# CBB-Proto-r02.net
KiCad netlist of a schematic drawn in EAGLE
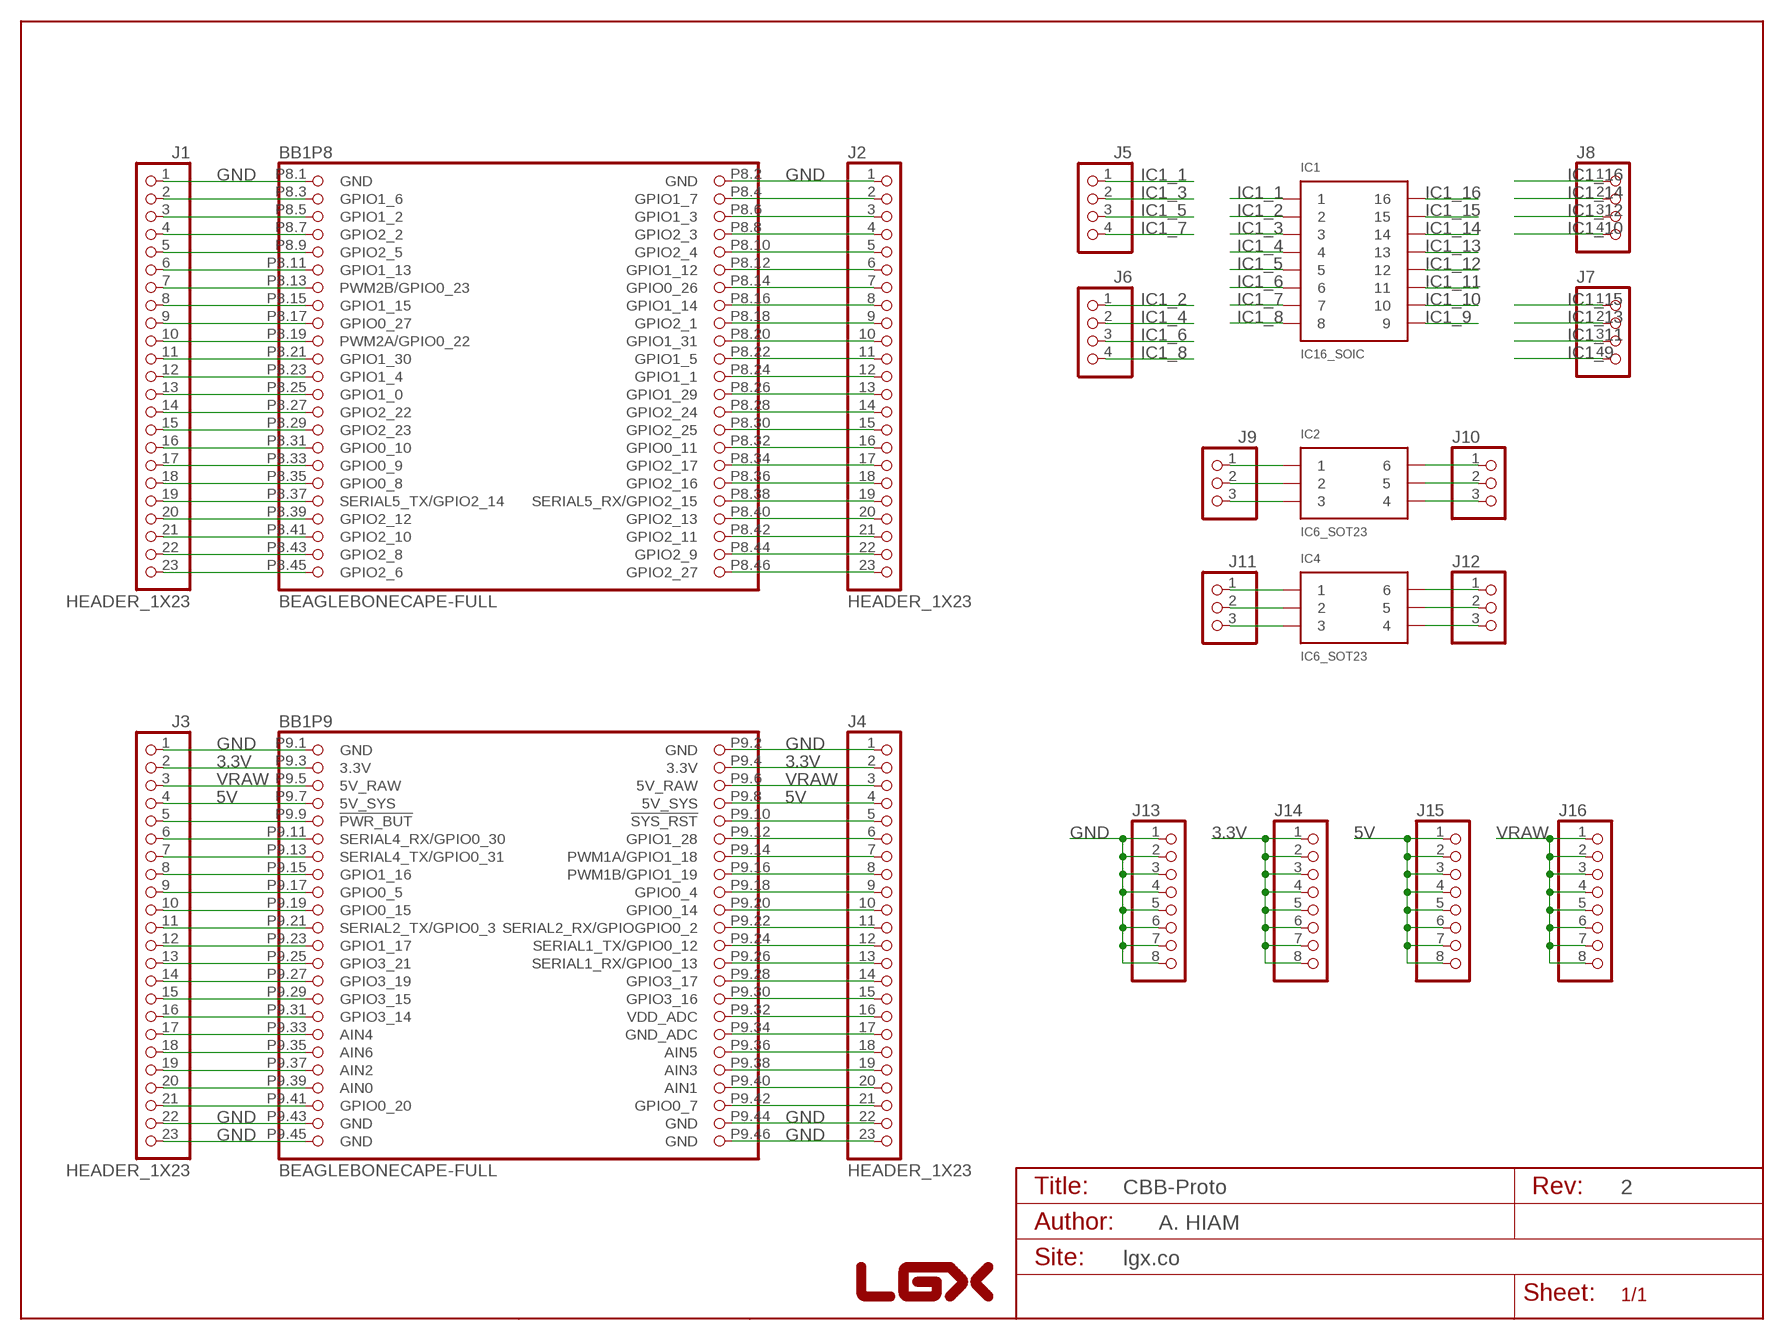
[diagram p0: schematic, sheet 1]

(export (version "E")
  (design (tool "Eeschema 10.0.6"))
  (components
    (comp (ref "BB1")
      (value "BEAGLEBONECAPE-FULL")
      (footprint "eagle-import:BEAGLEBONE_CAPE_FULL")
      (libsource (lib "eagle-import") (part "BEAGLEBONECAPE-FULL"))
    )
    (comp (ref "IC1")
      (value "IC16_SOIC")
      (footprint "eagle-import:SOIC16")
      (libsource (lib "eagle-import") (part "IC16_SOIC"))
    )
    (comp (ref "IC2")
      (value "IC6_SOT23")
      (footprint "eagle-import:SOT23-6")
      (libsource (lib "eagle-import") (part "IC6_SOT23"))
    )
    (comp (ref "IC4")
      (value "IC6_SOT23")
      (footprint "eagle-import:SOT23-6")
      (libsource (lib "eagle-import") (part "IC6_SOT23"))
    )
    (comp (ref "J1")
      (value "HEADER_1X23")
      (footprint "eagle-import:HEADER_1X23")
      (libsource (lib "eagle-import") (part "HEADER_1X23"))
    )
    (comp (ref "J2")
      (value "HEADER_1X23")
      (footprint "eagle-import:HEADER_1X23")
      (libsource (lib "eagle-import") (part "HEADER_1X23"))
    )
    (comp (ref "J3")
      (value "HEADER_1X23")
      (footprint "eagle-import:HEADER_1X23")
      (libsource (lib "eagle-import") (part "HEADER_1X23"))
    )
    (comp (ref "J4")
      (value "HEADER_1X23")
      (footprint "eagle-import:HEADER_1X23")
      (libsource (lib "eagle-import") (part "HEADER_1X23"))
    )
    (comp (ref "J5")
      (value "HEADER_1X4")
      (footprint "eagle-import:HEADER_1X4")
      (libsource (lib "eagle-import") (part "HEADER_1X4"))
    )
    (comp (ref "J6")
      (value "HEADER_1X4")
      (footprint "eagle-import:HEADER_1X4")
      (libsource (lib "eagle-import") (part "HEADER_1X4"))
    )
    (comp (ref "J7")
      (value "HEADER_1X4")
      (footprint "eagle-import:HEADER_1X4")
      (libsource (lib "eagle-import") (part "HEADER_1X4"))
    )
    (comp (ref "J8")
      (value "HEADER_1X4")
      (footprint "eagle-import:HEADER_1X4")
      (libsource (lib "eagle-import") (part "HEADER_1X4"))
    )
    (comp (ref "J9")
      (value "HEADER_1X3")
      (footprint "eagle-import:HEADER_1X3")
      (libsource (lib "eagle-import") (part "HEADER_1X3"))
    )
    (comp (ref "J10")
      (value "HEADER_1X3")
      (footprint "eagle-import:HEADER_1X3")
      (libsource (lib "eagle-import") (part "HEADER_1X3"))
    )
    (comp (ref "J11")
      (value "HEADER_1X3")
      (footprint "eagle-import:HEADER_1X3")
      (libsource (lib "eagle-import") (part "HEADER_1X3"))
    )
    (comp (ref "J12")
      (value "HEADER_1X3")
      (footprint "eagle-import:HEADER_1X3")
      (libsource (lib "eagle-import") (part "HEADER_1X3"))
    )
    (comp (ref "J13")
      (value "HEADER_1X8")
      (footprint "eagle-import:HEADER_1X8")
      (libsource (lib "eagle-import") (part "HEADER_1X8"))
    )
    (comp (ref "J14")
      (value "HEADER_1X8")
      (footprint "eagle-import:HEADER_1X8")
      (libsource (lib "eagle-import") (part "HEADER_1X8"))
    )
    (comp (ref "J15")
      (value "HEADER_1X8")
      (footprint "eagle-import:HEADER_1X8")
      (libsource (lib "eagle-import") (part "HEADER_1X8"))
    )
    (comp (ref "J16")
      (value "HEADER_1X8")
      (footprint "eagle-import:HEADER_1X8")
      (libsource (lib "eagle-import") (part "HEADER_1X8"))
    )
    (comp (ref "U$1")
      (value "LOGO-LGX")
      (footprint "eagle-import:LOGO-LGX")
      (libsource (lib "eagle-import") (part "LOGO-LGX"))
    )
  )
  (nets
    (net (code "1") (name "/3.3V") (class "Default")
      (node (ref "BB1") (pin "P9.3") (pinfunction "3.3V_P9.3") (pintype "power_in"))
      (node (ref "BB1") (pin "P9.4") (pinfunction "3.3V_P9.4") (pintype "power_in"))
      (node (ref "J14") (pin "1") (pinfunction "1_1") (pintype "passive"))
      (node (ref "J14") (pin "2") (pinfunction "2_2") (pintype "passive"))
      (node (ref "J14") (pin "3") (pinfunction "3_3") (pintype "passive"))
      (node (ref "J14") (pin "4") (pinfunction "4_4") (pintype "passive"))
      (node (ref "J14") (pin "5") (pinfunction "5_5") (pintype "passive"))
      (node (ref "J14") (pin "6") (pinfunction "6_6") (pintype "passive"))
      (node (ref "J14") (pin "7") (pinfunction "7_7") (pintype "passive"))
      (node (ref "J14") (pin "8") (pinfunction "8_8") (pintype "passive"))
      (node (ref "J3") (pin "2") (pinfunction "2_2") (pintype "passive"))
      (node (ref "J4") (pin "2") (pinfunction "2_2") (pintype "passive"))
    )
    (net (code "2") (name "/5V") (class "Default")
      (node (ref "BB1") (pin "P9.7") (pinfunction "5V_SYS_P9.7") (pintype "power_in"))
      (node (ref "BB1") (pin "P9.8") (pinfunction "5V_SYS_P9.8") (pintype "power_in"))
      (node (ref "J15") (pin "1") (pinfunction "1_1") (pintype "passive"))
      (node (ref "J15") (pin "2") (pinfunction "2_2") (pintype "passive"))
      (node (ref "J15") (pin "3") (pinfunction "3_3") (pintype "passive"))
      (node (ref "J15") (pin "4") (pinfunction "4_4") (pintype "passive"))
      (node (ref "J15") (pin "5") (pinfunction "5_5") (pintype "passive"))
      (node (ref "J15") (pin "6") (pinfunction "6_6") (pintype "passive"))
      (node (ref "J15") (pin "7") (pinfunction "7_7") (pintype "passive"))
      (node (ref "J15") (pin "8") (pinfunction "8_8") (pintype "passive"))
      (node (ref "J3") (pin "4") (pinfunction "4_4") (pintype "passive"))
      (node (ref "J4") (pin "4") (pinfunction "4_4") (pintype "passive"))
    )
    (net (code "3") (name "/GND") (class "Default")
      (node (ref "BB1") (pin "P8.1") (pinfunction "GND_P8.1") (pintype "power_in"))
      (node (ref "BB1") (pin "P8.2") (pinfunction "GND_P8.2") (pintype "power_in"))
      (node (ref "BB1") (pin "P9.1") (pinfunction "GND_P9.1") (pintype "power_in"))
      (node (ref "BB1") (pin "P9.2") (pinfunction "GND_P9.2") (pintype "power_in"))
      (node (ref "BB1") (pin "P9.43") (pinfunction "GND_P9.43") (pintype "bidirectional"))
      (node (ref "BB1") (pin "P9.44") (pinfunction "GND_P9.44") (pintype "bidirectional"))
      (node (ref "BB1") (pin "P9.45") (pinfunction "GND_P9.45") (pintype "bidirectional"))
      (node (ref "BB1") (pin "P9.46") (pinfunction "GND_P9.46") (pintype "bidirectional"))
      (node (ref "J1") (pin "1") (pinfunction "1_1") (pintype "passive"))
      (node (ref "J13") (pin "1") (pinfunction "1_1") (pintype "passive"))
      (node (ref "J13") (pin "2") (pinfunction "2_2") (pintype "passive"))
      (node (ref "J13") (pin "3") (pinfunction "3_3") (pintype "passive"))
      (node (ref "J13") (pin "4") (pinfunction "4_4") (pintype "passive"))
      (node (ref "J13") (pin "5") (pinfunction "5_5") (pintype "passive"))
      (node (ref "J13") (pin "6") (pinfunction "6_6") (pintype "passive"))
      (node (ref "J13") (pin "7") (pinfunction "7_7") (pintype "passive"))
      (node (ref "J13") (pin "8") (pinfunction "8_8") (pintype "passive"))
      (node (ref "J2") (pin "1") (pinfunction "1_1") (pintype "passive"))
      (node (ref "J3") (pin "1") (pinfunction "1_1") (pintype "passive"))
      (node (ref "J3") (pin "22") (pinfunction "22_22") (pintype "passive"))
      (node (ref "J3") (pin "23") (pinfunction "23_23") (pintype "passive"))
      (node (ref "J4") (pin "1") (pinfunction "1_1") (pintype "passive"))
      (node (ref "J4") (pin "22") (pinfunction "22_22") (pintype "passive"))
      (node (ref "J4") (pin "23") (pinfunction "23_23") (pintype "passive"))
    )
    (net (code "4") (name "/IC1_1") (class "Default")
      (node (ref "IC1") (pin "1") (pinfunction "1_1") (pintype "bidirectional"))
      (node (ref "J5") (pin "1") (pinfunction "1_1") (pintype "passive"))
    )
    (net (code "5") (name "/IC1_2") (class "Default")
      (node (ref "IC1") (pin "2") (pinfunction "2_2") (pintype "bidirectional"))
      (node (ref "J6") (pin "1") (pinfunction "1_1") (pintype "passive"))
    )
    (net (code "6") (name "/IC1_3") (class "Default")
      (node (ref "IC1") (pin "3") (pinfunction "3_3") (pintype "bidirectional"))
      (node (ref "J5") (pin "2") (pinfunction "2_2") (pintype "passive"))
    )
    (net (code "7") (name "/IC1_4") (class "Default")
      (node (ref "IC1") (pin "4") (pinfunction "4_4") (pintype "bidirectional"))
      (node (ref "J6") (pin "2") (pinfunction "2_2") (pintype "passive"))
    )
    (net (code "8") (name "/IC1_5") (class "Default")
      (node (ref "IC1") (pin "5") (pinfunction "5_5") (pintype "bidirectional"))
      (node (ref "J5") (pin "3") (pinfunction "3_3") (pintype "passive"))
    )
    (net (code "9") (name "/IC1_6") (class "Default")
      (node (ref "IC1") (pin "6") (pinfunction "6_6") (pintype "bidirectional"))
      (node (ref "J6") (pin "3") (pinfunction "3_3") (pintype "passive"))
    )
    (net (code "10") (name "/IC1_7") (class "Default")
      (node (ref "IC1") (pin "7") (pinfunction "7_7") (pintype "bidirectional"))
      (node (ref "J5") (pin "4") (pinfunction "4_4") (pintype "passive"))
    )
    (net (code "11") (name "/IC1_8") (class "Default")
      (node (ref "IC1") (pin "8") (pinfunction "8_8") (pintype "bidirectional"))
      (node (ref "J6") (pin "4") (pinfunction "4_4") (pintype "passive"))
    )
    (net (code "12") (name "/IC1_9") (class "Default")
      (node (ref "IC1") (pin "9") (pinfunction "9_9") (pintype "bidirectional"))
      (node (ref "J7") (pin "4") (pinfunction "4_4") (pintype "passive"))
    )
    (net (code "13") (name "/IC1_10") (class "Default")
      (node (ref "IC1") (pin "10") (pinfunction "10_10") (pintype "bidirectional"))
      (node (ref "J8") (pin "4") (pinfunction "4_4") (pintype "passive"))
    )
    (net (code "14") (name "/IC1_11") (class "Default")
      (node (ref "IC1") (pin "11") (pinfunction "11_11") (pintype "bidirectional"))
      (node (ref "J7") (pin "3") (pinfunction "3_3") (pintype "passive"))
    )
    (net (code "15") (name "/IC1_12") (class "Default")
      (node (ref "IC1") (pin "12") (pinfunction "12_12") (pintype "bidirectional"))
      (node (ref "J8") (pin "3") (pinfunction "3_3") (pintype "passive"))
    )
    (net (code "16") (name "/IC1_13") (class "Default")
      (node (ref "IC1") (pin "13") (pinfunction "13_13") (pintype "bidirectional"))
      (node (ref "J7") (pin "2") (pinfunction "2_2") (pintype "passive"))
    )
    (net (code "17") (name "/IC1_14") (class "Default")
      (node (ref "IC1") (pin "14") (pinfunction "14_14") (pintype "bidirectional"))
      (node (ref "J8") (pin "2") (pinfunction "2_2") (pintype "passive"))
    )
    (net (code "18") (name "/IC1_15") (class "Default")
      (node (ref "IC1") (pin "15") (pinfunction "15_15") (pintype "bidirectional"))
      (node (ref "J7") (pin "1") (pinfunction "1_1") (pintype "passive"))
    )
    (net (code "19") (name "/IC1_16") (class "Default")
      (node (ref "IC1") (pin "16") (pinfunction "16_16") (pintype "bidirectional"))
      (node (ref "J8") (pin "1") (pinfunction "1_1") (pintype "passive"))
    )
    (net (code "20") (name "/VRAW") (class "Default")
      (node (ref "BB1") (pin "P9.5") (pinfunction "5V_RAW_P9.5") (pintype "power_in"))
      (node (ref "BB1") (pin "P9.6") (pinfunction "5V_RAW_P9.6") (pintype "power_in"))
      (node (ref "J16") (pin "1") (pinfunction "1_1") (pintype "passive"))
      (node (ref "J16") (pin "2") (pinfunction "2_2") (pintype "passive"))
      (node (ref "J16") (pin "3") (pinfunction "3_3") (pintype "passive"))
      (node (ref "J16") (pin "4") (pinfunction "4_4") (pintype "passive"))
      (node (ref "J16") (pin "5") (pinfunction "5_5") (pintype "passive"))
      (node (ref "J16") (pin "6") (pinfunction "6_6") (pintype "passive"))
      (node (ref "J16") (pin "7") (pinfunction "7_7") (pintype "passive"))
      (node (ref "J16") (pin "8") (pinfunction "8_8") (pintype "passive"))
      (node (ref "J3") (pin "3") (pinfunction "3_3") (pintype "passive"))
      (node (ref "J4") (pin "3") (pinfunction "3_3") (pintype "passive"))
    )
    (net (code "21") (name "Net-(BB1A-GPIO0_8)") (class "Default")
      (node (ref "BB1") (pin "P8.35") (pinfunction "GPIO0_8_P8.35") (pintype "bidirectional"))
      (node (ref "J1") (pin "18") (pinfunction "18_18") (pintype "passive"))
    )
    (net (code "22") (name "Net-(BB1A-GPIO0_9)") (class "Default")
      (node (ref "BB1") (pin "P8.33") (pinfunction "GPIO0_9_P8.33") (pintype "bidirectional"))
      (node (ref "J1") (pin "17") (pinfunction "17_17") (pintype "passive"))
    )
    (net (code "23") (name "Net-(BB1A-GPIO0_10)") (class "Default")
      (node (ref "BB1") (pin "P8.31") (pinfunction "GPIO0_10_P8.31") (pintype "bidirectional"))
      (node (ref "J1") (pin "16") (pinfunction "16_16") (pintype "passive"))
    )
    (net (code "24") (name "Net-(BB1A-GPIO0_11)") (class "Default")
      (node (ref "BB1") (pin "P8.32") (pinfunction "GPIO0_11_P8.32") (pintype "bidirectional"))
      (node (ref "J2") (pin "16") (pinfunction "16_16") (pintype "passive"))
    )
    (net (code "25") (name "Net-(BB1A-GPIO0_26)") (class "Default")
      (node (ref "BB1") (pin "P8.14") (pinfunction "GPIO0_26_P8.14") (pintype "bidirectional"))
      (node (ref "J2") (pin "7") (pinfunction "7_7") (pintype "passive"))
    )
    (net (code "26") (name "Net-(BB1A-GPIO0_27)") (class "Default")
      (node (ref "BB1") (pin "P8.17") (pinfunction "GPIO0_27_P8.17") (pintype "bidirectional"))
      (node (ref "J1") (pin "9") (pinfunction "9_9") (pintype "passive"))
    )
    (net (code "27") (name "Net-(BB1A-GPIO1_0)") (class "Default")
      (node (ref "BB1") (pin "P8.25") (pinfunction "GPIO1_0_P8.25") (pintype "bidirectional"))
      (node (ref "J1") (pin "13") (pinfunction "13_13") (pintype "passive"))
    )
    (net (code "28") (name "Net-(BB1A-GPIO1_1)") (class "Default")
      (node (ref "BB1") (pin "P8.24") (pinfunction "GPIO1_1_P8.24") (pintype "bidirectional"))
      (node (ref "J2") (pin "12") (pinfunction "12_12") (pintype "passive"))
    )
    (net (code "29") (name "Net-(BB1A-GPIO1_2)") (class "Default")
      (node (ref "BB1") (pin "P8.5") (pinfunction "GPIO1_2_P8.5") (pintype "bidirectional"))
      (node (ref "J1") (pin "3") (pinfunction "3_3") (pintype "passive"))
    )
    (net (code "30") (name "Net-(BB1A-GPIO1_3)") (class "Default")
      (node (ref "BB1") (pin "P8.6") (pinfunction "GPIO1_3_P8.6") (pintype "bidirectional"))
      (node (ref "J2") (pin "3") (pinfunction "3_3") (pintype "passive"))
    )
    (net (code "31") (name "Net-(BB1A-GPIO1_4)") (class "Default")
      (node (ref "BB1") (pin "P8.23") (pinfunction "GPIO1_4_P8.23") (pintype "bidirectional"))
      (node (ref "J1") (pin "12") (pinfunction "12_12") (pintype "passive"))
    )
    (net (code "32") (name "Net-(BB1A-GPIO1_5)") (class "Default")
      (node (ref "BB1") (pin "P8.22") (pinfunction "GPIO1_5_P8.22") (pintype "bidirectional"))
      (node (ref "J2") (pin "11") (pinfunction "11_11") (pintype "passive"))
    )
    (net (code "33") (name "Net-(BB1A-GPIO1_6)") (class "Default")
      (node (ref "BB1") (pin "P8.3") (pinfunction "GPIO1_6_P8.3") (pintype "bidirectional"))
      (node (ref "J1") (pin "2") (pinfunction "2_2") (pintype "passive"))
    )
    (net (code "34") (name "Net-(BB1A-GPIO1_7)") (class "Default")
      (node (ref "BB1") (pin "P8.4") (pinfunction "GPIO1_7_P8.4") (pintype "bidirectional"))
      (node (ref "J2") (pin "2") (pinfunction "2_2") (pintype "passive"))
    )
    (net (code "35") (name "Net-(BB1A-GPIO1_12)") (class "Default")
      (node (ref "BB1") (pin "P8.12") (pinfunction "GPIO1_12_P8.12") (pintype "bidirectional"))
      (node (ref "J2") (pin "6") (pinfunction "6_6") (pintype "passive"))
    )
    (net (code "36") (name "Net-(BB1A-GPIO1_13)") (class "Default")
      (node (ref "BB1") (pin "P8.11") (pinfunction "GPIO1_13_P8.11") (pintype "bidirectional"))
      (node (ref "J1") (pin "6") (pinfunction "6_6") (pintype "passive"))
    )
    (net (code "37") (name "Net-(BB1A-GPIO1_14)") (class "Default")
      (node (ref "BB1") (pin "P8.16") (pinfunction "GPIO1_14_P8.16") (pintype "bidirectional"))
      (node (ref "J2") (pin "8") (pinfunction "8_8") (pintype "passive"))
    )
    (net (code "38") (name "Net-(BB1A-GPIO1_15)") (class "Default")
      (node (ref "BB1") (pin "P8.15") (pinfunction "GPIO1_15_P8.15") (pintype "bidirectional"))
      (node (ref "J1") (pin "8") (pinfunction "8_8") (pintype "passive"))
    )
    (net (code "39") (name "Net-(BB1A-GPIO1_29)") (class "Default")
      (node (ref "BB1") (pin "P8.26") (pinfunction "GPIO1_29_P8.26") (pintype "bidirectional"))
      (node (ref "J2") (pin "13") (pinfunction "13_13") (pintype "passive"))
    )
    (net (code "40") (name "Net-(BB1A-GPIO1_30)") (class "Default")
      (node (ref "BB1") (pin "P8.21") (pinfunction "GPIO1_30_P8.21") (pintype "bidirectional"))
      (node (ref "J1") (pin "11") (pinfunction "11_11") (pintype "passive"))
    )
    (net (code "41") (name "Net-(BB1A-GPIO1_31)") (class "Default")
      (node (ref "BB1") (pin "P8.20") (pinfunction "GPIO1_31_P8.20") (pintype "bidirectional"))
      (node (ref "J2") (pin "10") (pinfunction "10_10") (pintype "passive"))
    )
    (net (code "42") (name "Net-(BB1A-GPIO2_1)") (class "Default")
      (node (ref "BB1") (pin "P8.18") (pinfunction "GPIO2_1_P8.18") (pintype "bidirectional"))
      (node (ref "J2") (pin "9") (pinfunction "9_9") (pintype "passive"))
    )
    (net (code "43") (name "Net-(BB1A-GPIO2_2)") (class "Default")
      (node (ref "BB1") (pin "P8.7") (pinfunction "GPIO2_2_P8.7") (pintype "bidirectional"))
      (node (ref "J1") (pin "4") (pinfunction "4_4") (pintype "passive"))
    )
    (net (code "44") (name "Net-(BB1A-GPIO2_3)") (class "Default")
      (node (ref "BB1") (pin "P8.8") (pinfunction "GPIO2_3_P8.8") (pintype "bidirectional"))
      (node (ref "J2") (pin "4") (pinfunction "4_4") (pintype "passive"))
    )
    (net (code "45") (name "Net-(BB1A-GPIO2_4)") (class "Default")
      (node (ref "BB1") (pin "P8.10") (pinfunction "GPIO2_4_P8.10") (pintype "bidirectional"))
      (node (ref "J2") (pin "5") (pinfunction "5_5") (pintype "passive"))
    )
    (net (code "46") (name "Net-(BB1A-GPIO2_5)") (class "Default")
      (node (ref "BB1") (pin "P8.9") (pinfunction "GPIO2_5_P8.9") (pintype "bidirectional"))
      (node (ref "J1") (pin "5") (pinfunction "5_5") (pintype "passive"))
    )
    (net (code "47") (name "Net-(BB1A-GPIO2_6)") (class "Default")
      (node (ref "BB1") (pin "P8.45") (pinfunction "GPIO2_6_P8.45") (pintype "bidirectional"))
      (node (ref "J1") (pin "23") (pinfunction "23_23") (pintype "passive"))
    )
    (net (code "48") (name "Net-(BB1A-GPIO2_8)") (class "Default")
      (node (ref "BB1") (pin "P8.43") (pinfunction "GPIO2_8_P8.43") (pintype "bidirectional"))
      (node (ref "J1") (pin "22") (pinfunction "22_22") (pintype "passive"))
    )
    (net (code "49") (name "Net-(BB1A-GPIO2_9)") (class "Default")
      (node (ref "BB1") (pin "P8.44") (pinfunction "GPIO2_9_P8.44") (pintype "bidirectional"))
      (node (ref "J2") (pin "22") (pinfunction "22_22") (pintype "passive"))
    )
    (net (code "50") (name "Net-(BB1A-GPIO2_10)") (class "Default")
      (node (ref "BB1") (pin "P8.41") (pinfunction "GPIO2_10_P8.41") (pintype "bidirectional"))
      (node (ref "J1") (pin "21") (pinfunction "21_21") (pintype "passive"))
    )
    (net (code "51") (name "Net-(BB1A-GPIO2_11)") (class "Default")
      (node (ref "BB1") (pin "P8.42") (pinfunction "GPIO2_11_P8.42") (pintype "bidirectional"))
      (node (ref "J2") (pin "21") (pinfunction "21_21") (pintype "passive"))
    )
    (net (code "52") (name "Net-(BB1A-GPIO2_12)") (class "Default")
      (node (ref "BB1") (pin "P8.39") (pinfunction "GPIO2_12_P8.39") (pintype "bidirectional"))
      (node (ref "J1") (pin "20") (pinfunction "20_20") (pintype "passive"))
    )
    (net (code "53") (name "Net-(BB1A-GPIO2_13)") (class "Default")
      (node (ref "BB1") (pin "P8.40") (pinfunction "GPIO2_13_P8.40") (pintype "bidirectional"))
      (node (ref "J2") (pin "20") (pinfunction "20_20") (pintype "passive"))
    )
    (net (code "54") (name "Net-(BB1A-GPIO2_16)") (class "Default")
      (node (ref "BB1") (pin "P8.36") (pinfunction "GPIO2_16_P8.36") (pintype "bidirectional"))
      (node (ref "J2") (pin "18") (pinfunction "18_18") (pintype "passive"))
    )
    (net (code "55") (name "Net-(BB1A-GPIO2_17)") (class "Default")
      (node (ref "BB1") (pin "P8.34") (pinfunction "GPIO2_17_P8.34") (pintype "bidirectional"))
      (node (ref "J2") (pin "17") (pinfunction "17_17") (pintype "passive"))
    )
    (net (code "56") (name "Net-(BB1A-GPIO2_22)") (class "Default")
      (node (ref "BB1") (pin "P8.27") (pinfunction "GPIO2_22_P8.27") (pintype "bidirectional"))
      (node (ref "J1") (pin "14") (pinfunction "14_14") (pintype "passive"))
    )
    (net (code "57") (name "Net-(BB1A-GPIO2_23)") (class "Default")
      (node (ref "BB1") (pin "P8.29") (pinfunction "GPIO2_23_P8.29") (pintype "bidirectional"))
      (node (ref "J1") (pin "15") (pinfunction "15_15") (pintype "passive"))
    )
    (net (code "58") (name "Net-(BB1A-GPIO2_24)") (class "Default")
      (node (ref "BB1") (pin "P8.28") (pinfunction "GPIO2_24_P8.28") (pintype "bidirectional"))
      (node (ref "J2") (pin "14") (pinfunction "14_14") (pintype "passive"))
    )
    (net (code "59") (name "Net-(BB1A-GPIO2_25)") (class "Default")
      (node (ref "BB1") (pin "P8.30") (pinfunction "GPIO2_25_P8.30") (pintype "bidirectional"))
      (node (ref "J2") (pin "15") (pinfunction "15_15") (pintype "passive"))
    )
    (net (code "60") (name "Net-(BB1A-GPIO2_27)") (class "Default")
      (node (ref "BB1") (pin "P8.46") (pinfunction "GPIO2_27_P8.46") (pintype "bidirectional"))
      (node (ref "J2") (pin "23") (pinfunction "23_23") (pintype "passive"))
    )
    (net (code "61") (name "Net-(BB1A-PWM2A{slash}GPIO0_22)") (class "Default")
      (node (ref "BB1") (pin "P8.19") (pinfunction "PWM2A/GPIO0_22_P8.19") (pintype "bidirectional"))
      (node (ref "J1") (pin "10") (pinfunction "10_10") (pintype "passive"))
    )
    (net (code "62") (name "Net-(BB1A-PWM2B{slash}GPIO0_23)") (class "Default")
      (node (ref "BB1") (pin "P8.13") (pinfunction "PWM2B/GPIO0_23_P8.13") (pintype "bidirectional"))
      (node (ref "J1") (pin "7") (pinfunction "7_7") (pintype "passive"))
    )
    (net (code "63") (name "Net-(BB1A-SERIAL5_RX{slash}GPIO2_15)") (class "Default")
      (node (ref "BB1") (pin "P8.38") (pinfunction "SERIAL5_RX/GPIO2_15_P8.38") (pintype "bidirectional"))
      (node (ref "J2") (pin "19") (pinfunction "19_19") (pintype "passive"))
    )
    (net (code "64") (name "Net-(BB1A-SERIAL5_TX{slash}GPIO2_14)") (class "Default")
      (node (ref "BB1") (pin "P8.37") (pinfunction "SERIAL5_TX/GPIO2_14_P8.37") (pintype "bidirectional"))
      (node (ref "J1") (pin "19") (pinfunction "19_19") (pintype "passive"))
    )
    (net (code "65") (name "Net-(BB1B-AIN0)") (class "Default")
      (node (ref "BB1") (pin "P9.39") (pinfunction "AIN0_P9.39") (pintype "input"))
      (node (ref "J3") (pin "20") (pinfunction "20_20") (pintype "passive"))
    )
    (net (code "66") (name "Net-(BB1B-AIN1)") (class "Default")
      (node (ref "BB1") (pin "P9.40") (pinfunction "AIN1_P9.40") (pintype "input"))
      (node (ref "J4") (pin "20") (pinfunction "20_20") (pintype "passive"))
    )
    (net (code "67") (name "Net-(BB1B-AIN2)") (class "Default")
      (node (ref "BB1") (pin "P9.37") (pinfunction "AIN2_P9.37") (pintype "input"))
      (node (ref "J3") (pin "19") (pinfunction "19_19") (pintype "passive"))
    )
    (net (code "68") (name "Net-(BB1B-AIN3)") (class "Default")
      (node (ref "BB1") (pin "P9.38") (pinfunction "AIN3_P9.38") (pintype "input"))
      (node (ref "J4") (pin "19") (pinfunction "19_19") (pintype "passive"))
    )
    (net (code "69") (name "Net-(BB1B-AIN4)") (class "Default")
      (node (ref "BB1") (pin "P9.33") (pinfunction "AIN4_P9.33") (pintype "input"))
      (node (ref "J3") (pin "17") (pinfunction "17_17") (pintype "passive"))
    )
    (net (code "70") (name "Net-(BB1B-AIN5)") (class "Default")
      (node (ref "BB1") (pin "P9.36") (pinfunction "AIN5_P9.36") (pintype "input"))
      (node (ref "J4") (pin "18") (pinfunction "18_18") (pintype "passive"))
    )
    (net (code "71") (name "Net-(BB1B-AIN6)") (class "Default")
      (node (ref "BB1") (pin "P9.35") (pinfunction "AIN6_P9.35") (pintype "input"))
      (node (ref "J3") (pin "18") (pinfunction "18_18") (pintype "passive"))
    )
    (net (code "72") (name "Net-(BB1B-GND_ADC)") (class "Default")
      (node (ref "BB1") (pin "P9.34") (pinfunction "GND_ADC_P9.34") (pintype "bidirectional"))
      (node (ref "J4") (pin "17") (pinfunction "17_17") (pintype "passive"))
    )
    (net (code "73") (name "Net-(BB1B-GPIO0_4)") (class "Default")
      (node (ref "BB1") (pin "P9.18") (pinfunction "GPIO0_4_P9.18") (pintype "bidirectional"))
      (node (ref "J4") (pin "9") (pinfunction "9_9") (pintype "passive"))
    )
    (net (code "74") (name "Net-(BB1B-GPIO0_5)") (class "Default")
      (node (ref "BB1") (pin "P9.17") (pinfunction "GPIO0_5_P9.17") (pintype "bidirectional"))
      (node (ref "J3") (pin "9") (pinfunction "9_9") (pintype "passive"))
    )
    (net (code "75") (name "Net-(BB1B-GPIO0_7)") (class "Default")
      (node (ref "BB1") (pin "P9.42") (pinfunction "GPIO0_7_P9.42") (pintype "bidirectional"))
      (node (ref "J4") (pin "21") (pinfunction "21_21") (pintype "passive"))
    )
    (net (code "76") (name "Net-(BB1B-GPIO0_14)") (class "Default")
      (node (ref "BB1") (pin "P9.20") (pinfunction "GPIO0_14_P9.20") (pintype "bidirectional"))
      (node (ref "J4") (pin "10") (pinfunction "10_10") (pintype "passive"))
    )
    (net (code "77") (name "Net-(BB1B-GPIO0_15)") (class "Default")
      (node (ref "BB1") (pin "P9.19") (pinfunction "GPIO0_15_P9.19") (pintype "bidirectional"))
      (node (ref "J3") (pin "10") (pinfunction "10_10") (pintype "passive"))
    )
    (net (code "78") (name "Net-(BB1B-GPIO0_20)") (class "Default")
      (node (ref "BB1") (pin "P9.41") (pinfunction "GPIO0_20_P9.41") (pintype "bidirectional"))
      (node (ref "J3") (pin "21") (pinfunction "21_21") (pintype "passive"))
    )
    (net (code "79") (name "Net-(BB1B-GPIO1_16)") (class "Default")
      (node (ref "BB1") (pin "P9.15") (pinfunction "GPIO1_16_P9.15") (pintype "bidirectional"))
      (node (ref "J3") (pin "8") (pinfunction "8_8") (pintype "passive"))
    )
    (net (code "80") (name "Net-(BB1B-GPIO1_17)") (class "Default")
      (node (ref "BB1") (pin "P9.23") (pinfunction "GPIO1_17_P9.23") (pintype "bidirectional"))
      (node (ref "J3") (pin "12") (pinfunction "12_12") (pintype "passive"))
    )
    (net (code "81") (name "Net-(BB1B-GPIO1_28)") (class "Default")
      (node (ref "BB1") (pin "P9.12") (pinfunction "GPIO1_28_P9.12") (pintype "bidirectional"))
      (node (ref "J4") (pin "6") (pinfunction "6_6") (pintype "passive"))
    )
    (net (code "82") (name "Net-(BB1B-GPIO3_14)") (class "Default")
      (node (ref "BB1") (pin "P9.31") (pinfunction "GPIO3_14_P9.31") (pintype "bidirectional"))
      (node (ref "J3") (pin "16") (pinfunction "16_16") (pintype "passive"))
    )
    (net (code "83") (name "Net-(BB1B-GPIO3_15)") (class "Default")
      (node (ref "BB1") (pin "P9.29") (pinfunction "GPIO3_15_P9.29") (pintype "bidirectional"))
      (node (ref "J3") (pin "15") (pinfunction "15_15") (pintype "passive"))
    )
    (net (code "84") (name "Net-(BB1B-GPIO3_16)") (class "Default")
      (node (ref "BB1") (pin "P9.30") (pinfunction "GPIO3_16_P9.30") (pintype "bidirectional"))
      (node (ref "J4") (pin "15") (pinfunction "15_15") (pintype "passive"))
    )
    (net (code "85") (name "Net-(BB1B-GPIO3_17)") (class "Default")
      (node (ref "BB1") (pin "P9.28") (pinfunction "GPIO3_17_P9.28") (pintype "bidirectional"))
      (node (ref "J4") (pin "14") (pinfunction "14_14") (pintype "passive"))
    )
    (net (code "86") (name "Net-(BB1B-GPIO3_19)") (class "Default")
      (node (ref "BB1") (pin "P9.27") (pinfunction "GPIO3_19_P9.27") (pintype "bidirectional"))
      (node (ref "J3") (pin "14") (pinfunction "14_14") (pintype "passive"))
    )
    (net (code "87") (name "Net-(BB1B-GPIO3_21)") (class "Default")
      (node (ref "BB1") (pin "P9.25") (pinfunction "GPIO3_21_P9.25") (pintype "bidirectional"))
      (node (ref "J3") (pin "13") (pinfunction "13_13") (pintype "passive"))
    )
    (net (code "88") (name "Net-(BB1B-PWM1A{slash}GPIO1_18)") (class "Default")
      (node (ref "BB1") (pin "P9.14") (pinfunction "PWM1A/GPIO1_18_P9.14") (pintype "bidirectional"))
      (node (ref "J4") (pin "7") (pinfunction "7_7") (pintype "passive"))
    )
    (net (code "89") (name "Net-(BB1B-PWM1B{slash}GPIO1_19)") (class "Default")
      (node (ref "BB1") (pin "P9.16") (pinfunction "PWM1B/GPIO1_19_P9.16") (pintype "bidirectional"))
      (node (ref "J4") (pin "8") (pinfunction "8_8") (pintype "passive"))
    )
    (net (code "90") (name "Net-(BB1B-SERIAL1_RX{slash}GPIO0_13)") (class "Default")
      (node (ref "BB1") (pin "P9.26") (pinfunction "SERIAL1_RX/GPIO0_13_P9.26") (pintype "bidirectional"))
      (node (ref "J4") (pin "13") (pinfunction "13_13") (pintype "passive"))
    )
    (net (code "91") (name "Net-(BB1B-SERIAL1_TX{slash}GPIO0_12)") (class "Default")
      (node (ref "BB1") (pin "P9.24") (pinfunction "SERIAL1_TX/GPIO0_12_P9.24") (pintype "bidirectional"))
      (node (ref "J4") (pin "12") (pinfunction "12_12") (pintype "passive"))
    )
    (net (code "92") (name "Net-(BB1B-SERIAL2_RX{slash}GPIOGPIO0_2)") (class "Default")
      (node (ref "BB1") (pin "P9.22") (pinfunction "SERIAL2_RX/GPIOGPIO0_2_P9.22") (pintype "bidirectional"))
      (node (ref "J4") (pin "11") (pinfunction "11_11") (pintype "passive"))
    )
    (net (code "93") (name "Net-(BB1B-SERIAL2_TX{slash}GPIO0_3)") (class "Default")
      (node (ref "BB1") (pin "P9.21") (pinfunction "SERIAL2_TX/GPIO0_3_P9.21") (pintype "bidirectional"))
      (node (ref "J3") (pin "11") (pinfunction "11_11") (pintype "passive"))
    )
    (net (code "94") (name "Net-(BB1B-SERIAL4_RX{slash}GPIO0_30)") (class "Default")
      (node (ref "BB1") (pin "P9.11") (pinfunction "SERIAL4_RX/GPIO0_30_P9.11") (pintype "bidirectional"))
      (node (ref "J3") (pin "6") (pinfunction "6_6") (pintype "passive"))
    )
    (net (code "95") (name "Net-(BB1B-SERIAL4_TX{slash}GPIO0_31)") (class "Default")
      (node (ref "BB1") (pin "P9.13") (pinfunction "SERIAL4_TX/GPIO0_31_P9.13") (pintype "bidirectional"))
      (node (ref "J3") (pin "7") (pinfunction "7_7") (pintype "passive"))
    )
    (net (code "96") (name "Net-(BB1B-VDD_ADC)") (class "Default")
      (node (ref "BB1") (pin "P9.32") (pinfunction "VDD_ADC_P9.32") (pintype "bidirectional"))
      (node (ref "J4") (pin "16") (pinfunction "16_16") (pintype "passive"))
    )
    (net (code "97") (name "Net-(BB1B-~{PWR_BUT})") (class "Default")
      (node (ref "BB1") (pin "P9.9") (pinfunction "~{PWR_BUT}_P9.9") (pintype "input"))
      (node (ref "J3") (pin "5") (pinfunction "5_5") (pintype "passive"))
    )
    (net (code "98") (name "Net-(BB1B-~{SYS_RST})") (class "Default")
      (node (ref "BB1") (pin "P9.10") (pinfunction "~{SYS_RST}_P9.10") (pintype "input"))
      (node (ref "J4") (pin "5") (pinfunction "5_5") (pintype "passive"))
    )
    (net (code "99") (name "Net-(IC2-Pad1)") (class "Default")
      (node (ref "IC2") (pin "1") (pinfunction "1_1") (pintype "bidirectional"))
      (node (ref "J9") (pin "1") (pinfunction "1_1") (pintype "passive"))
    )
    (net (code "100") (name "Net-(IC2-Pad2)") (class "Default")
      (node (ref "IC2") (pin "2") (pinfunction "2_2") (pintype "bidirectional"))
      (node (ref "J9") (pin "2") (pinfunction "2_2") (pintype "passive"))
    )
    (net (code "101") (name "Net-(IC2-Pad3)") (class "Default")
      (node (ref "IC2") (pin "3") (pinfunction "3_3") (pintype "bidirectional"))
      (node (ref "J9") (pin "3") (pinfunction "3_3") (pintype "passive"))
    )
    (net (code "102") (name "Net-(IC2-Pad4)") (class "Default")
      (node (ref "IC2") (pin "4") (pinfunction "4_4") (pintype "bidirectional"))
      (node (ref "J10") (pin "3") (pinfunction "3_3") (pintype "passive"))
    )
    (net (code "103") (name "Net-(IC2-Pad5)") (class "Default")
      (node (ref "IC2") (pin "5") (pinfunction "5_5") (pintype "bidirectional"))
      (node (ref "J10") (pin "2") (pinfunction "2_2") (pintype "passive"))
    )
    (net (code "104") (name "Net-(IC2-Pad6)") (class "Default")
      (node (ref "IC2") (pin "6") (pinfunction "6_6") (pintype "bidirectional"))
      (node (ref "J10") (pin "1") (pinfunction "1_1") (pintype "passive"))
    )
    (net (code "105") (name "Net-(IC4-Pad1)") (class "Default")
      (node (ref "IC4") (pin "1") (pinfunction "1_1") (pintype "bidirectional"))
      (node (ref "J11") (pin "1") (pinfunction "1_1") (pintype "passive"))
    )
    (net (code "106") (name "Net-(IC4-Pad2)") (class "Default")
      (node (ref "IC4") (pin "2") (pinfunction "2_2") (pintype "bidirectional"))
      (node (ref "J11") (pin "2") (pinfunction "2_2") (pintype "passive"))
    )
    (net (code "107") (name "Net-(IC4-Pad3)") (class "Default")
      (node (ref "IC4") (pin "3") (pinfunction "3_3") (pintype "bidirectional"))
      (node (ref "J11") (pin "3") (pinfunction "3_3") (pintype "passive"))
    )
    (net (code "108") (name "Net-(IC4-Pad4)") (class "Default")
      (node (ref "IC4") (pin "4") (pinfunction "4_4") (pintype "bidirectional"))
      (node (ref "J12") (pin "3") (pinfunction "3_3") (pintype "passive"))
    )
    (net (code "109") (name "Net-(IC4-Pad5)") (class "Default")
      (node (ref "IC4") (pin "5") (pinfunction "5_5") (pintype "bidirectional"))
      (node (ref "J12") (pin "2") (pinfunction "2_2") (pintype "passive"))
    )
    (net (code "110") (name "Net-(IC4-Pad6)") (class "Default")
      (node (ref "IC4") (pin "6") (pinfunction "6_6") (pintype "bidirectional"))
      (node (ref "J12") (pin "1") (pinfunction "1_1") (pintype "passive"))
    )
  )
)
